# Sheet1.net
KiCad netlist of a schematic drawn in Altium Designer
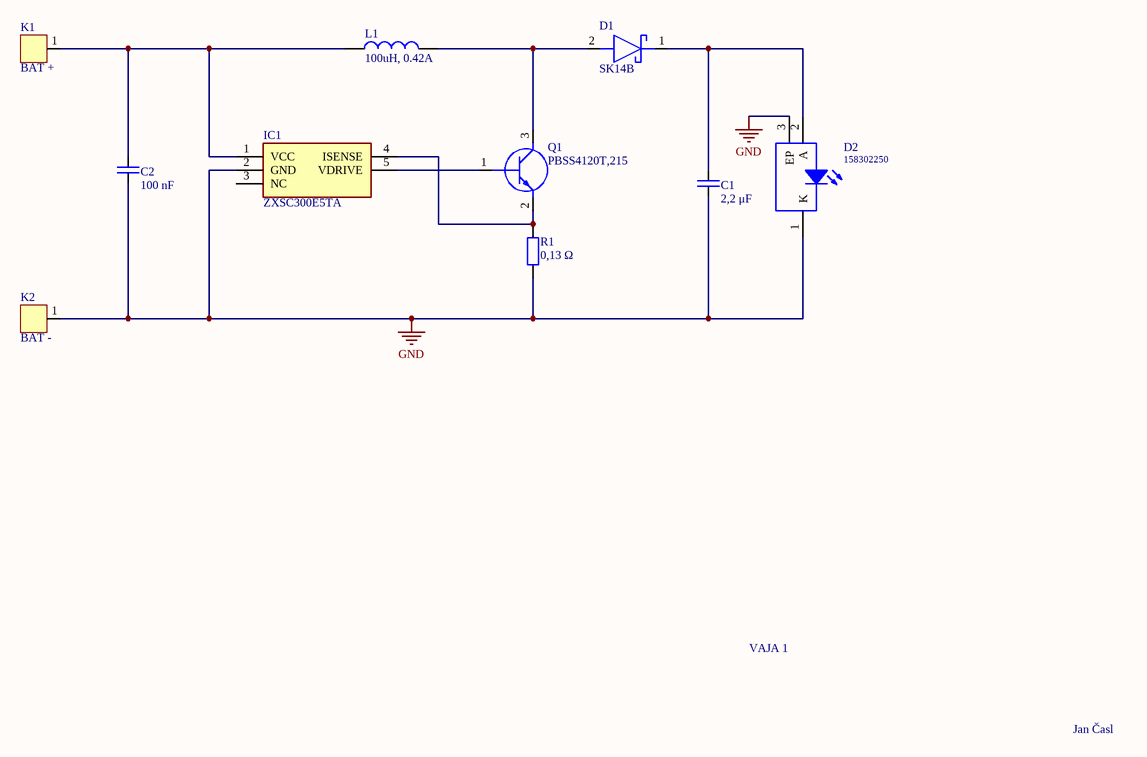
[diagram p0: Sheet1.SchDoc]

(export (version "E")
  (design (tool "Eeschema 10.0.6"))
  (components
    (comp (ref "C1")
      (value "2,2 μF")
      (footprint "C2012_0805I_M")
      (description "Capacitor")
      (libsource (lib "General") (part "C"))
    )
    (comp (ref "C2")
      (value "100 nF")
      (footprint "C2012_0805I_M")
      (description "Capacitor")
      (libsource (lib "General") (part "C"))
    )
    (comp (ref "D1")
      (value "SK14B")
      (footprint "SamacSys:DIOM5236X261N")
      (description "Schottky Diode")
      (fields (field (name "MOUSER PART NUMBER") "821-SK14B"))
      (libsource (lib "*") (part "SK14B"))
    )
    (comp (ref "D2")
      (value "158302250")
      (footprint "WL-SWTP_3022_L3W2.1H0.8")
      (description "WL-SWTP SMT White Top view PLCC, size 3022, Daylight, 3.2V, 120deg")
      (fields (field (name "MANUFACTURER") "Wurth Elektronik"))
      (libsource (lib "158302250_Altium_WL-SWTP_rev20a") (part "158302250"))
    )
    (comp (ref "IC1")
      (value "ZXSC300E5TA")
      (footprint "SamacSys:SOT95P270X145-5N")
      (description "Integrated Circuit")
      (fields (field (name "MOUSER PART NUMBER") "522-ZXSC300E5TA"))
      (libsource (lib "*") (part "ZXSC300E5TA"))
    )
    (comp (ref "K1")
      (value "BAT +")
      (footprint "H1x1")
      (description "Header 1x1 (male)")
      (libsource (lib "Kon_Tipk") (part "H1x1"))
    )
    (comp (ref "K2")
      (value "BAT -")
      (footprint "H1x1")
      (description "Header 1x1 (male)")
      (libsource (lib "Kon_Tipk") (part "H1x1"))
    )
    (comp (ref "L1")
      (value "100uH, 0.42A")
      (footprint "WE-LQFS_4818")
      (description "WE-LQFS SMT Power Inductor, size 4818, 100uH, 0.42A")
      (fields
        (field (name "MANUFACTURER") "Wurth Elektronik")
        (field (name "MANUFACTURER PART NUMBER") "74406042101")
      )
      (libsource (lib "74406042101_Altium_WE-LQFS_rev20a") (part "74406042101"))
    )
    (comp (ref "Q1")
      (value "PBSS4120T,215")
      (footprint "SamacSys:SOT95P230X110-3N")
      (description "Transistor BJT NPN")
      (fields (field (name "MOUSER PART NUMBER") "771-PBSS4120T215"))
      (libsource (lib "*") (part "PBSS4120T,215"))
    )
    (comp (ref "R1")
      (value "0,13 Ω")
      (footprint "R2012_0805I_M")
      (description "R")
      (libsource (lib "General") (part "R"))
    )
  )
  (nets
    (net (code "1") (name "GND") (class "Default")
      (node (ref "C1") (pin "2") (pinfunction "2_2") (pintype "passive"))
      (node (ref "C2") (pin "2") (pinfunction "2_2") (pintype "passive"))
      (node (ref "D2") (pin "1") (pinfunction "K_1") (pintype "passive"))
      (node (ref "D2") (pin "3") (pinfunction "EP_3") (pintype "passive"))
      (node (ref "IC1") (pin "2") (pinfunction "GND_2") (pintype "passive"))
      (node (ref "K2") (pin "1") (pinfunction "1_1") (pintype "passive"))
      (node (ref "R1") (pin "2") (pintype "passive"))
    )
    (net (code "2") (name "Net-(D1-A)") (class "Default")
      (node (ref "D1") (pin "2") (pinfunction "A_2") (pintype "passive"))
      (node (ref "L1") (pin "2") (pinfunction "2_2") (pintype "passive"))
      (node (ref "Q1") (pin "3") (pinfunction "C_3") (pintype "passive"))
    )
    (net (code "3") (name "Net-(D1-K)") (class "Default")
      (node (ref "C1") (pin "1") (pinfunction "1_1") (pintype "passive"))
      (node (ref "D1") (pin "1") (pinfunction "K_1") (pintype "passive"))
      (node (ref "D2") (pin "2") (pinfunction "A_2") (pintype "passive"))
    )
    (net (code "4") (name "Net-(IC1-ISENSE)") (class "Default")
      (node (ref "IC1") (pin "4") (pinfunction "ISENSE_4") (pintype "passive"))
      (node (ref "Q1") (pin "2") (pinfunction "E_2") (pintype "passive"))
      (node (ref "R1") (pin "1") (pintype "passive"))
    )
    (net (code "5") (name "Net-(IC1-VCC)") (class "Default")
      (node (ref "C2") (pin "1") (pinfunction "1_1") (pintype "passive"))
      (node (ref "IC1") (pin "1") (pinfunction "VCC_1") (pintype "passive"))
      (node (ref "K1") (pin "1") (pinfunction "1_1") (pintype "passive"))
      (node (ref "L1") (pin "1") (pinfunction "1_1") (pintype "passive"))
    )
    (net (code "6") (name "Net-(IC1-VDRIVE)") (class "Default")
      (node (ref "IC1") (pin "5") (pinfunction "VDRIVE_5") (pintype "passive"))
      (node (ref "Q1") (pin "1") (pinfunction "B_1") (pintype "passive"))
    )
    (net (code "7") (name "unconnected-(IC1-NC-Pad3)") (class "Default")
      (node (ref "IC1") (pin "3") (pinfunction "NC_3") (pintype "passive"))
    )
  )
)
